# Controller_AC.net
KiCad netlist of a schematic drawn in Altium Designer
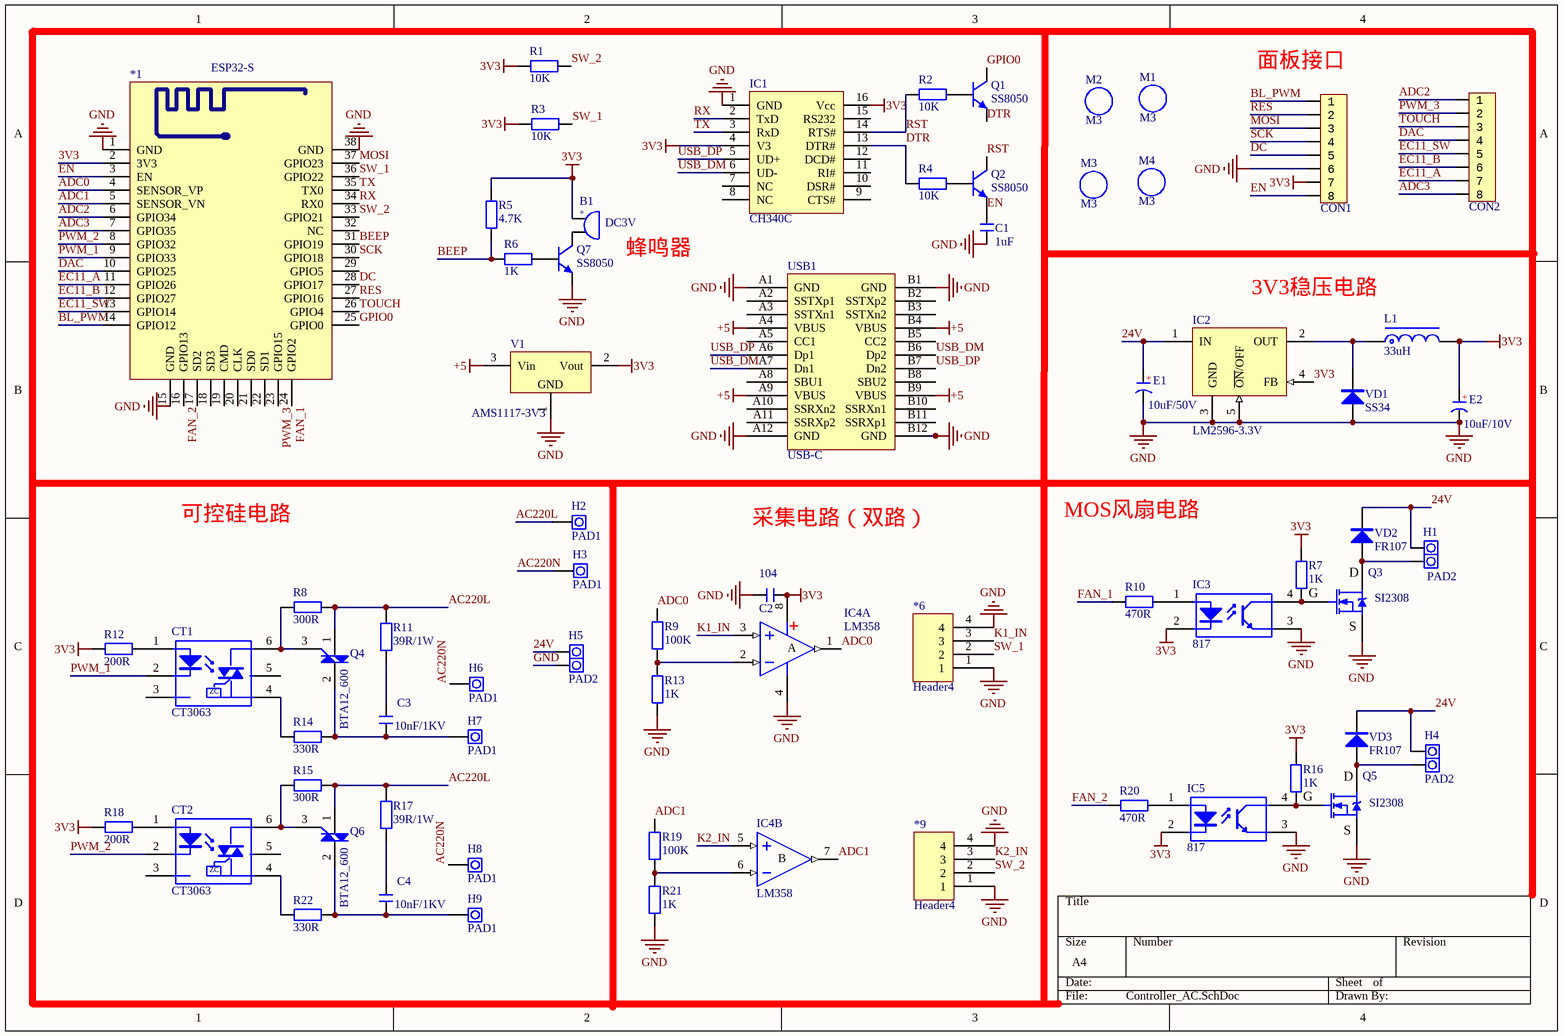
[diagram p0: Controller_AC.SchDoc]

(export (version "E")
  (design (tool "Eeschema 10.0.6"))
  (components
    (comp (ref "*1")
      (value "ESP32-S")
      (footprint "WIFIM-SMD_ESP32-C3S-2M")
      (libsource (lib "ExtendBoard") (part "ESP32-S"))
    )
    (comp (ref "*6")
      (value "Header4")
      (footprint "HDR2.54-LI-4P")
      (libsource (lib "ExtendBoard") (part "Header4"))
    )
    (comp (ref "*9")
      (value "Header4")
      (footprint "HDR2.54-LI-4P")
      (libsource (lib "ExtendBoard") (part "Header4"))
    )
    (comp (ref "B1")
      (value "DC3V")
      (footprint "BEEP 5x9x5.5")
      (description "蜂鸣器")
      (fields (field (name "版权归属") "源创客"))
      (libsource (lib "HeatPlatform") (part "BEEP"))
    )
    (comp (ref "C1")
      (value "1uF")
      (footprint "C 0603")
      (description "无极性贴片电容")
      (fields (field (name "版权归属") "源创客"))
      (libsource (lib "ExtendBoard") (part "C"))
    )
    (comp (ref "C2")
      (value "104")
      (footprint "C 0603")
      (description "无极性贴片电容")
      (fields (field (name "版权归属") "源创客"))
      (libsource (lib "ExtendBoard") (part "C"))
    )
    (comp (ref "C3")
      (value "10nF/1KV")
      (footprint "C 1206_L")
      (description "无极性贴片电容")
      (fields (field (name "版权归属") "源创客"))
      (libsource (lib "ExtendBoard") (part "C"))
    )
    (comp (ref "C4")
      (value "10nF/1KV")
      (footprint "C 1206_L")
      (description "无极性贴片电容")
      (fields (field (name "版权归属") "源创客"))
      (libsource (lib "ExtendBoard") (part "C"))
    )
    (comp (ref "CON1")
      (value "FFC_0.5_8")
      (footprint "FFC_0.5_8")
      (description "FFC")
      (libsource (lib "ExtendBoard") (part "FFC_0.5_8"))
    )
    (comp (ref "CON2")
      (value "FFC_0.5_8")
      (footprint "FFC_0.5_8")
      (description "FFC")
      (libsource (lib "ExtendBoard") (part "FFC_0.5_8"))
    )
    (comp (ref "CT1")
      (value "CT3063")
      (footprint "SMD-6-CT3063")
      (description "线性光耦（过零检测）")
      (fields (field (name "版权归属") "源创客"))
      (libsource (lib "ExtendBoard") (part "CT3063"))
    )
    (comp (ref "CT2")
      (value "CT3063")
      (footprint "SMD-6-CT3063")
      (description "线性光耦（过零检测）")
      (fields (field (name "版权归属") "源创客"))
      (libsource (lib "ExtendBoard") (part "CT3063"))
    )
    (comp (ref "E1")
      (value "10uF/50V")
      (footprint "CT 6*6 - C")
      (description "贴片固态电容")
      (fields (field (name "版权归属") "源创客"))
      (libsource (lib "ExtendBoard") (part "C-CT"))
    )
    (comp (ref "E2")
      (value "10uF/10V")
      (footprint "CT 6*6 - C")
      (description "贴片固态电容")
      (fields (field (name "版权归属") "源创客"))
      (libsource (lib "ExtendBoard") (part "C-CT"))
    )
    (comp (ref "H1")
      (value "PAD2")
      (footprint "PAD2-2.0")
      (description "引线焊盘")
      (libsource (lib "ExtendBoard") (part "PAD2"))
    )
    (comp (ref "H2")
      (value "PAD1")
      (footprint "PAD1-C")
      (description "引线焊盘")
      (libsource (lib "ExtendBoard") (part "PAD1"))
    )
    (comp (ref "H3")
      (value "PAD1")
      (footprint "PAD1-B")
      (description "引线焊盘")
      (libsource (lib "ExtendBoard") (part "PAD1"))
    )
    (comp (ref "H4")
      (value "PAD2")
      (footprint "PAD2-2.0")
      (description "引线焊盘")
      (libsource (lib "ExtendBoard") (part "PAD2"))
    )
    (comp (ref "H5")
      (value "PAD2")
      (footprint "PAD2-5.08")
      (description "引线焊盘")
      (libsource (lib "ExtendBoard") (part "PAD2"))
    )
    (comp (ref "H6")
      (value "PAD1")
      (footprint "PAD1-C")
      (description "引线焊盘")
      (libsource (lib "ExtendBoard") (part "PAD1"))
    )
    (comp (ref "H7")
      (value "PAD1")
      (footprint "PAD1-C")
      (description "引线焊盘")
      (libsource (lib "ExtendBoard") (part "PAD1"))
    )
    (comp (ref "H8")
      (value "PAD1")
      (footprint "PAD1-C")
      (description "引线焊盘")
      (libsource (lib "ExtendBoard") (part "PAD1"))
    )
    (comp (ref "H9")
      (value "PAD1")
      (footprint "PAD1-C")
      (description "引线焊盘")
      (libsource (lib "ExtendBoard") (part "PAD1"))
    )
    (comp (ref "IC1")
      (value "CH340C")
      (footprint "SOP16_N")
      (description "串口转USB")
      (libsource (lib "ExtendBoard") (part "CH340C"))
    )
    (comp (ref "IC2")
      (value "LM2596-3.3V")
      (footprint "TO263-5A")
      (description "DC降压芯片")
      (fields (field (name "版权归属") "源创客"))
      (libsource (lib "ExtendBoard") (part "LM2596"))
    )
    (comp (ref "IC3")
      (value "817")
      (footprint "SOP4-W2.54_L")
      (description "线性光耦")
      (fields (field (name "版权归属") "源创客"))
      (libsource (lib "ExtendBoard") (part "817"))
    )
    (comp (ref "IC4")
      (value "LM358")
      (footprint "SOP8_N")
      (description "双路运放")
      (libsource (lib "ExtendBoard") (part "LM358"))
    )
    (comp (ref "IC5")
      (value "817")
      (footprint "SOP4-W2.54_L")
      (description "线性光耦")
      (fields (field (name "版权归属") "源创客"))
      (libsource (lib "ExtendBoard") (part "817"))
    )
    (comp (ref "L1")
      (value "33uH")
      (footprint "CDRH127")
      (description "功率屏蔽电感")
      (fields (field (name "版权归属") "源创客"))
      (libsource (lib "ExtendBoard") (part "L-CDRH"))
    )
    (comp (ref "M1")
      (value "M3")
      (footprint "M3 125X200")
      (description "铜柱孔")
      (libsource (lib "ExtendBoard") (part "M3"))
    )
    (comp (ref "M2")
      (value "M3")
      (footprint "M3 125X200")
      (description "铜柱孔")
      (libsource (lib "ExtendBoard") (part "M3"))
    )
    (comp (ref "M3")
      (value "M3")
      (footprint "M3 125X200")
      (description "铜柱孔")
      (libsource (lib "ExtendBoard") (part "M3"))
    )
    (comp (ref "M4")
      (value "M3")
      (footprint "M3 125X200")
      (description "铜柱孔")
      (libsource (lib "ExtendBoard") (part "M3"))
    )
    (comp (ref "Q1")
      (value "SS8050")
      (footprint "SOT23-3N")
      (description "高频放大-NPN型")
      (fields (field (name "版权归属") "源创客"))
      (libsource (lib "ExtendBoard") (part "8050-SMD"))
    )
    (comp (ref "Q2")
      (value "SS8050")
      (footprint "SOT23-3N")
      (description "高频放大-NPN型")
      (fields (field (name "版权归属") "源创客"))
      (libsource (lib "ExtendBoard") (part "8050-SMD"))
    )
    (comp (ref "Q3")
      (value "SI2308")
      (footprint "SOT23-3N")
      (description "N沟道场效应管")
      (fields (field (name "版权归属") "源创客"))
      (libsource (lib "ExtendBoard") (part "SI2302"))
    )
    (comp (ref "Q4")
      (value "BTA12_600")
      (footprint "TO220A")
      (description "双向可控硅")
      (fields (field (name "版权归属") "源创客"))
      (libsource (lib "ExtendBoard") (part "BTA12_600"))
    )
    (comp (ref "Q5")
      (value "SI2308")
      (footprint "SOT23-3N")
      (description "N沟道场效应管")
      (fields (field (name "版权归属") "源创客"))
      (libsource (lib "ExtendBoard") (part "SI2302"))
    )
    (comp (ref "Q6")
      (value "BTA12_600")
      (footprint "TO220A")
      (description "双向可控硅")
      (fields (field (name "版权归属") "源创客"))
      (libsource (lib "ExtendBoard") (part "BTA12_600"))
    )
    (comp (ref "Q7")
      (value "SS8050")
      (footprint "SOT23-3N")
      (description "高频放大-NPN型")
      (fields (field (name "版权归属") "源创客"))
      (libsource (lib "ExtendBoard") (part "8050-SMD"))
    )
    (comp (ref "R1")
      (value "10K")
      (footprint "R 0603")
      (description "贴片电阻")
      (fields (field (name "版权归属") "源创客"))
      (libsource (lib "ExtendBoard") (part "R"))
    )
    (comp (ref "R2")
      (value "10K")
      (footprint "R 0603")
      (description "贴片电阻")
      (fields (field (name "版权归属") "源创客"))
      (libsource (lib "ExtendBoard") (part "R"))
    )
    (comp (ref "R3")
      (value "10K")
      (footprint "R 0603")
      (description "贴片电阻")
      (fields (field (name "版权归属") "源创客"))
      (libsource (lib "ExtendBoard") (part "R"))
    )
    (comp (ref "R4")
      (value "10K")
      (footprint "R 0603")
      (description "贴片电阻")
      (fields (field (name "版权归属") "源创客"))
      (libsource (lib "ExtendBoard") (part "R"))
    )
    (comp (ref "R5")
      (value "4.7K")
      (footprint "R 0603")
      (description "贴片电阻")
      (fields (field (name "版权归属") "源创客"))
      (libsource (lib "HeatPlatform") (part "R"))
    )
    (comp (ref "R6")
      (value "1K")
      (footprint "R 0603")
      (description "贴片电阻")
      (fields (field (name "版权归属") "源创客"))
      (libsource (lib "HeatPlatform") (part "R"))
    )
    (comp (ref "R7")
      (value "1K")
      (footprint "R 0603")
      (description "贴片电阻")
      (fields (field (name "版权归属") "源创客"))
      (libsource (lib "ExtendBoard") (part "R"))
    )
    (comp (ref "R8")
      (value "300R")
      (footprint "R 0603")
      (description "贴片电阻")
      (fields (field (name "版权归属") "源创客"))
      (libsource (lib "ExtendBoard") (part "R"))
    )
    (comp (ref "R9")
      (value "100K")
      (footprint "R 0603")
      (description "贴片电阻")
      (fields (field (name "版权归属") "源创客"))
      (libsource (lib "ExtendBoard") (part "R"))
    )
    (comp (ref "R10")
      (value "470R")
      (footprint "R 0603")
      (description "贴片电阻")
      (fields (field (name "版权归属") "源创客"))
      (libsource (lib "ExtendBoard") (part "R"))
    )
    (comp (ref "R11")
      (value "39R/1W")
      (footprint "R 2512_L")
      (description "贴片电阻")
      (fields (field (name "版权归属") "源创客"))
      (libsource (lib "ExtendBoard") (part "R"))
    )
    (comp (ref "R12")
      (value "200R")
      (footprint "R 0603")
      (description "贴片电阻")
      (fields (field (name "版权归属") "源创客"))
      (libsource (lib "ExtendBoard") (part "R"))
    )
    (comp (ref "R13")
      (value "1K")
      (footprint "R 0603")
      (description "贴片电阻")
      (fields (field (name "版权归属") "源创客"))
      (libsource (lib "ExtendBoard") (part "R"))
    )
    (comp (ref "R14")
      (value "330R")
      (footprint "R 0603")
      (description "贴片电阻")
      (fields (field (name "版权归属") "源创客"))
      (libsource (lib "ExtendBoard") (part "R"))
    )
    (comp (ref "R15")
      (value "300R")
      (footprint "R 0603")
      (description "贴片电阻")
      (fields (field (name "版权归属") "源创客"))
      (libsource (lib "ExtendBoard") (part "R"))
    )
    (comp (ref "R16")
      (value "1K")
      (footprint "R 0603")
      (description "贴片电阻")
      (fields (field (name "版权归属") "源创客"))
      (libsource (lib "ExtendBoard") (part "R"))
    )
    (comp (ref "R17")
      (value "39R/1W")
      (footprint "R 2512_L")
      (description "贴片电阻")
      (fields (field (name "版权归属") "源创客"))
      (libsource (lib "ExtendBoard") (part "R"))
    )
    (comp (ref "R18")
      (value "200R")
      (footprint "R 0603")
      (description "贴片电阻")
      (fields (field (name "版权归属") "源创客"))
      (libsource (lib "ExtendBoard") (part "R"))
    )
    (comp (ref "R19")
      (value "100K")
      (footprint "R 0603")
      (description "贴片电阻")
      (fields (field (name "版权归属") "源创客"))
      (libsource (lib "ExtendBoard") (part "R"))
    )
    (comp (ref "R20")
      (value "470R")
      (footprint "R 0603")
      (description "贴片电阻")
      (fields (field (name "版权归属") "源创客"))
      (libsource (lib "ExtendBoard") (part "R"))
    )
    (comp (ref "R21")
      (value "1K")
      (footprint "R 0603")
      (description "贴片电阻")
      (fields (field (name "版权归属") "源创客"))
      (libsource (lib "ExtendBoard") (part "R"))
    )
    (comp (ref "R22")
      (value "330R")
      (footprint "R 0603")
      (description "贴片电阻")
      (fields (field (name "版权归属") "源创客"))
      (libsource (lib "ExtendBoard") (part "R"))
    )
    (comp (ref "USB1")
      (value "USB-C")
      (footprint "USB Type-C-16Pin_A")
      (description "USB-C型母接口")
      (libsource (lib "ExtendBoard") (part "USB-C/S"))
    )
    (comp (ref "V1")
      (value "AMS1117-3V3")
      (footprint "SOT223_L")
      (description "三端稳压芯片")
      (fields (field (name "版权归属") "源创客"))
      (libsource (lib "ExtendBoard") (part "AMS1117"))
    )
    (comp (ref "VD1")
      (value "SS34")
      (footprint "SMA")
      (description "肖特基二极管")
      (fields (field (name "版权归属") "源创客"))
      (libsource (lib "ExtendBoard") (part "SS34"))
    )
    (comp (ref "VD2")
      (value "FR107")
      (footprint "SMA")
      (description "肖特基二极管")
      (fields (field (name "版权归属") "源创客"))
      (libsource (lib "ExtendBoard") (part "SS34"))
    )
    (comp (ref "VD3")
      (value "FR107")
      (footprint "SMA")
      (description "肖特基二极管")
      (fields (field (name "版权归属") "源创客"))
      (libsource (lib "ExtendBoard") (part "SS34"))
    )
  )
  (nets
    (net (code "1") (name "+5") (class "Default")
      (node (ref "USB1") (pin "A4") (pinfunction "VBUS_A4") (pintype "passive"))
      (node (ref "USB1") (pin "A9") (pinfunction "VBUS_A9") (pintype "passive"))
      (node (ref "USB1") (pin "B4") (pinfunction "VBUS_B4") (pintype "passive"))
      (node (ref "USB1") (pin "B9") (pinfunction "VBUS_B9") (pintype "passive"))
      (node (ref "V1") (pin "3") (pinfunction "Vin_3") (pintype "passive"))
    )
    (net (code "2") (name "/24V") (class "Default")
      (node (ref "E1") (pin "1") (pinfunction "A_1") (pintype "passive"))
      (node (ref "H1") (pin "1") (pinfunction "1_1") (pintype "passive"))
      (node (ref "H4") (pin "1") (pinfunction "1_1") (pintype "passive"))
      (node (ref "H5") (pin "1") (pinfunction "1_1") (pintype "passive"))
      (node (ref "IC2") (pin "1") (pinfunction "IN_1") (pintype "power_in"))
      (node (ref "VD2") (pin "2") (pinfunction "K_2") (pintype "passive"))
      (node (ref "VD3") (pin "2") (pinfunction "K_2") (pintype "passive"))
    )
    (net (code "3") (name "/AC220L") (class "Default")
      (node (ref "H2") (pin "1") (pinfunction "1_1") (pintype "passive"))
      (node (ref "Q4") (pin "1") (pinfunction "A1_1") (pintype "passive"))
      (node (ref "Q6") (pin "1") (pinfunction "A1_1") (pintype "passive"))
      (node (ref "R11") (pin "2") (pinfunction "2_2") (pintype "passive"))
      (node (ref "R15") (pin "2") (pinfunction "2_2") (pintype "passive"))
      (node (ref "R17") (pin "2") (pinfunction "2_2") (pintype "passive"))
      (node (ref "R8") (pin "2") (pinfunction "2_2") (pintype "passive"))
    )
    (net (code "4") (name "/AC220N") (class "Default")
      (node (ref "H3") (pin "1") (pinfunction "1_1") (pintype "passive"))
      (node (ref "H6") (pin "1") (pinfunction "1_1") (pintype "passive"))
      (node (ref "H8") (pin "1") (pinfunction "1_1") (pintype "passive"))
    )
    (net (code "5") (name "/ADC0") (class "Default")
      (node (ref "*1") (pin "4") (pinfunction "SENSOR_VP_4") (pintype "passive"))
      (node (ref "IC4") (pin "1") (pinfunction "OUT_1") (pintype "output"))
      (node (ref "R9") (pin "2") (pinfunction "2_2") (pintype "passive"))
    )
    (net (code "6") (name "/ADC1") (class "Default")
      (node (ref "*1") (pin "5") (pinfunction "SENSOR_VN_5") (pintype "passive"))
      (node (ref "IC4") (pin "7") (pinfunction "OUT_7") (pintype "output"))
      (node (ref "R19") (pin "2") (pinfunction "2_2") (pintype "passive"))
    )
    (net (code "7") (name "/ADC2") (class "Default")
      (node (ref "*1") (pin "6") (pinfunction "GPIO34_6") (pintype "passive"))
      (node (ref "CON2") (pin "1") (pinfunction "1_1") (pintype "passive"))
    )
    (net (code "8") (name "/ADC3") (class "Default")
      (node (ref "*1") (pin "7") (pinfunction "GPIO35_7") (pintype "passive"))
      (node (ref "CON2") (pin "8") (pinfunction "8_8") (pintype "passive"))
    )
    (net (code "9") (name "/BEEP") (class "Default")
      (node (ref "*1") (pin "31") (pinfunction "GPIO19_31") (pintype "passive"))
      (node (ref "R5") (pin "1") (pinfunction "1_1") (pintype "passive"))
      (node (ref "R6") (pin "1") (pinfunction "1_1") (pintype "passive"))
    )
    (net (code "10") (name "/BL_PWM") (class "Default")
      (node (ref "*1") (pin "14") (pinfunction "GPIO12_14") (pintype "passive"))
      (node (ref "CON1") (pin "1") (pinfunction "1_1") (pintype "passive"))
    )
    (net (code "11") (name "/DAC") (class "Default")
      (node (ref "*1") (pin "10") (pinfunction "GPIO25_10") (pintype "passive"))
      (node (ref "CON2") (pin "4") (pinfunction "4_4") (pintype "passive"))
    )
    (net (code "12") (name "/DC") (class "Default")
      (node (ref "*1") (pin "28") (pinfunction "GPIO17_28") (pintype "passive"))
      (node (ref "CON1") (pin "5") (pinfunction "5_5") (pintype "passive"))
    )
    (net (code "13") (name "/DTR") (class "Default")
      (node (ref "IC1") (pin "13") (pinfunction "DTR#_13") (pintype "passive"))
      (node (ref "Q1") (pin "2") (pinfunction "E_2") (pintype "passive"))
      (node (ref "R4") (pin "1") (pinfunction "1_1") (pintype "passive"))
    )
    (net (code "14") (name "/EC11_A") (class "Default")
      (node (ref "*1") (pin "11") (pinfunction "GPIO26_11") (pintype "passive"))
      (node (ref "CON2") (pin "7") (pinfunction "7_7") (pintype "passive"))
    )
    (net (code "15") (name "/EC11_B") (class "Default")
      (node (ref "*1") (pin "12") (pinfunction "GPIO27_12") (pintype "passive"))
      (node (ref "CON2") (pin "6") (pinfunction "6_6") (pintype "passive"))
    )
    (net (code "16") (name "/EC11_SW") (class "Default")
      (node (ref "*1") (pin "13") (pinfunction "GPIO14_13") (pintype "passive"))
      (node (ref "CON2") (pin "5") (pinfunction "5_5") (pintype "passive"))
    )
    (net (code "17") (name "/EN") (class "Default")
      (node (ref "*1") (pin "3") (pinfunction "EN_3") (pintype "passive"))
      (node (ref "C1") (pin "2") (pinfunction "2_2") (pintype "passive"))
      (node (ref "CON1") (pin "8") (pinfunction "8_8") (pintype "passive"))
      (node (ref "Q2") (pin "2") (pinfunction "E_2") (pintype "passive"))
    )
    (net (code "18") (name "/FAN_1") (class "Default")
      (node (ref "*1") (pin "24") (pinfunction "GPIO2_24") (pintype "passive"))
      (node (ref "R10") (pin "2") (pinfunction "2_2") (pintype "passive"))
    )
    (net (code "19") (name "/FAN_2") (class "Default")
      (node (ref "*1") (pin "16") (pinfunction "GPIO13_16") (pintype "passive"))
      (node (ref "R20") (pin "2") (pinfunction "2_2") (pintype "passive"))
    )
    (net (code "20") (name "/GPIO0") (class "Default")
      (node (ref "*1") (pin "25") (pinfunction "GPIO0_25") (pintype "passive"))
      (node (ref "Q1") (pin "3") (pinfunction "C_3") (pintype "passive"))
    )
    (net (code "21") (name "/K1_IN") (class "Default")
      (node (ref "*6") (pin "3") (pinfunction "3_3") (pintype "passive"))
      (node (ref "IC4") (pin "3") (pinfunction "IN+_3") (pintype "input"))
    )
    (net (code "22") (name "/K2_IN") (class "Default")
      (node (ref "*9") (pin "3") (pinfunction "3_3") (pintype "passive"))
      (node (ref "IC4") (pin "5") (pinfunction "IN+_5") (pintype "input"))
    )
    (net (code "23") (name "/MOSI") (class "Default")
      (node (ref "*1") (pin "37") (pinfunction "GPIO23_37") (pintype "passive"))
      (node (ref "CON1") (pin "3") (pinfunction "3_3") (pintype "passive"))
    )
    (net (code "24") (name "/PWM_1") (class "Default")
      (node (ref "*1") (pin "9") (pinfunction "GPIO33_9") (pintype "passive"))
      (node (ref "CT1") (pin "2") (pinfunction "C_2") (pintype "passive"))
    )
    (net (code "25") (name "/PWM_2") (class "Default")
      (node (ref "*1") (pin "8") (pinfunction "GPIO32_8") (pintype "passive"))
      (node (ref "CT2") (pin "2") (pinfunction "C_2") (pintype "passive"))
    )
    (net (code "26") (name "/PWM_3") (class "Default")
      (node (ref "*1") (pin "23") (pinfunction "GPIO15_23") (pintype "passive"))
      (node (ref "CON2") (pin "2") (pinfunction "2_2") (pintype "passive"))
    )
    (net (code "27") (name "/RES") (class "Default")
      (node (ref "*1") (pin "27") (pinfunction "GPIO16_27") (pintype "passive"))
      (node (ref "CON1") (pin "2") (pinfunction "2_2") (pintype "passive"))
    )
    (net (code "28") (name "/RST") (class "Default")
      (node (ref "IC1") (pin "14") (pinfunction "RTS#_14") (pintype "passive"))
      (node (ref "Q2") (pin "3") (pinfunction "C_3") (pintype "passive"))
      (node (ref "R2") (pin "1") (pinfunction "1_1") (pintype "passive"))
    )
    (net (code "29") (name "/RX") (class "Default")
      (node (ref "*1") (pin "34") (pinfunction "RX0_34") (pintype "passive"))
      (node (ref "IC1") (pin "2") (pinfunction "TxD_2") (pintype "passive"))
    )
    (net (code "30") (name "/SCK") (class "Default")
      (node (ref "*1") (pin "30") (pinfunction "GPIO18_30") (pintype "passive"))
      (node (ref "CON1") (pin "4") (pinfunction "4_4") (pintype "passive"))
    )
    (net (code "31") (name "/SW_1") (class "Default")
      (node (ref "*1") (pin "36") (pinfunction "GPIO22_36") (pintype "passive"))
      (node (ref "*6") (pin "2") (pinfunction "2_2") (pintype "passive"))
      (node (ref "R3") (pin "1") (pinfunction "1_1") (pintype "passive"))
    )
    (net (code "32") (name "/SW_2") (class "Default")
      (node (ref "*1") (pin "33") (pinfunction "GPIO21_33") (pintype "passive"))
      (node (ref "*9") (pin "2") (pinfunction "2_2") (pintype "passive"))
      (node (ref "R1") (pin "2") (pinfunction "2_2") (pintype "passive"))
    )
    (net (code "33") (name "/TOUCH") (class "Default")
      (node (ref "*1") (pin "26") (pinfunction "GPIO4_26") (pintype "passive"))
      (node (ref "CON2") (pin "3") (pinfunction "3_3") (pintype "passive"))
    )
    (net (code "34") (name "/TX") (class "Default")
      (node (ref "*1") (pin "35") (pinfunction "TX0_35") (pintype "passive"))
      (node (ref "IC1") (pin "3") (pinfunction "RxD_3") (pintype "passive"))
    )
    (net (code "35") (name "/USB_DM") (class "Default")
      (node (ref "IC1") (pin "6") (pinfunction "UD-_6") (pintype "passive"))
      (node (ref "USB1") (pin "A7") (pinfunction "Dn1_A7") (pintype "passive"))
      (node (ref "USB1") (pin "B6") (pinfunction "Dp2_B6") (pintype "passive"))
    )
    (net (code "36") (name "/USB_DP") (class "Default")
      (node (ref "IC1") (pin "5") (pinfunction "UD+_5") (pintype "passive"))
      (node (ref "USB1") (pin "A6") (pinfunction "Dp1_A6") (pintype "passive"))
      (node (ref "USB1") (pin "B7") (pinfunction "Dn2_B7") (pintype "passive"))
    )
    (net (code "37") (name "3V3") (class "Default")
      (node (ref "*1") (pin "2") (pinfunction "3V3_2") (pintype "passive"))
      (node (ref "B1") (pin "1") (pinfunction "1_1") (pintype "passive"))
      (node (ref "C2") (pin "2") (pinfunction "2_2") (pintype "passive"))
      (node (ref "CON1") (pin "7") (pinfunction "7_7") (pintype "passive"))
      (node (ref "E2") (pin "1") (pinfunction "A_1") (pintype "passive"))
      (node (ref "IC1") (pin "16") (pinfunction "Vcc_16") (pintype "passive"))
      (node (ref "IC1") (pin "4") (pinfunction "V3_4") (pintype "passive"))
      (node (ref "IC2") (pin "4") (pinfunction "FB_4") (pintype "input"))
      (node (ref "IC3") (pin "2") (pinfunction "K_2") (pintype "passive"))
      (node (ref "IC4") (pin "8") (pinfunction "V+_8") (pintype "power_in"))
      (node (ref "IC5") (pin "2") (pinfunction "K_2") (pintype "passive"))
      (node (ref "L1") (pin "2") (pinfunction "2_2") (pintype "passive"))
      (node (ref "R1") (pin "1") (pinfunction "1_1") (pintype "passive"))
      (node (ref "R12") (pin "1") (pinfunction "1_1") (pintype "passive"))
      (node (ref "R16") (pin "2") (pinfunction "2_2") (pintype "passive"))
      (node (ref "R18") (pin "1") (pinfunction "1_1") (pintype "passive"))
      (node (ref "R3") (pin "2") (pinfunction "2_2") (pintype "passive"))
      (node (ref "R5") (pin "2") (pinfunction "2_2") (pintype "passive"))
      (node (ref "R7") (pin "2") (pinfunction "2_2") (pintype "passive"))
      (node (ref "V1") (pin "2") (pinfunction "Vout_2") (pintype "passive"))
    )
    (net (code "38") (name "GND") (class "Default")
      (node (ref "*1") (pin "1") (pinfunction "GND_1") (pintype "passive"))
      (node (ref "*1") (pin "15") (pinfunction "GND_15") (pintype "passive"))
      (node (ref "*1") (pin "38") (pinfunction "GND_38") (pintype "passive"))
      (node (ref "*6") (pin "1") (pinfunction "1_1") (pintype "passive"))
      (node (ref "*6") (pin "4") (pinfunction "4_4") (pintype "passive"))
      (node (ref "*9") (pin "1") (pinfunction "1_1") (pintype "passive"))
      (node (ref "*9") (pin "4") (pinfunction "4_4") (pintype "passive"))
      (node (ref "C1") (pin "1") (pinfunction "1_1") (pintype "passive"))
      (node (ref "C2") (pin "1") (pinfunction "1_1") (pintype "passive"))
      (node (ref "CON1") (pin "6") (pinfunction "6_6") (pintype "passive"))
      (node (ref "E1") (pin "2") (pinfunction "K_2") (pintype "passive"))
      (node (ref "E2") (pin "2") (pinfunction "K_2") (pintype "passive"))
      (node (ref "H5") (pin "2") (pinfunction "2_2") (pintype "passive"))
      (node (ref "IC1") (pin "1") (pinfunction "GND_1") (pintype "passive"))
      (node (ref "IC2") (pin "3") (pinfunction "GND_3") (pintype "power_in"))
      (node (ref "IC2") (pin "5") (pinfunction "~{ON}/OFF_5") (pintype "input"))
      (node (ref "IC3") (pin "3") (pinfunction "E_3") (pintype "passive"))
      (node (ref "IC4") (pin "4") (pinfunction "V-_4") (pintype "power_in"))
      (node (ref "IC5") (pin "3") (pinfunction "E_3") (pintype "passive"))
      (node (ref "Q3") (pin "2") (pinfunction "S_2") (pintype "passive"))
      (node (ref "Q5") (pin "2") (pinfunction "S_2") (pintype "passive"))
      (node (ref "Q7") (pin "2") (pinfunction "E_2") (pintype "passive"))
      (node (ref "R13") (pin "1") (pinfunction "1_1") (pintype "passive"))
      (node (ref "R21") (pin "1") (pinfunction "1_1") (pintype "passive"))
      (node (ref "USB1") (pin "A1") (pinfunction "GND_A1") (pintype "passive"))
      (node (ref "USB1") (pin "A12") (pinfunction "GND_A12") (pintype "passive"))
      (node (ref "USB1") (pin "B1") (pinfunction "GND_B1") (pintype "passive"))
      (node (ref "USB1") (pin "B12") (pinfunction "GND_B12") (pintype "passive"))
      (node (ref "V1") (pin "1") (pinfunction "GND_1") (pintype "passive"))
      (node (ref "VD1") (pin "1") (pinfunction "A_1") (pintype "passive"))
    )
    (net (code "39") (name "Net-(C3-Pad2)") (class "Default")
      (node (ref "C3") (pin "2") (pinfunction "2_2") (pintype "passive"))
      (node (ref "R11") (pin "1") (pinfunction "1_1") (pintype "passive"))
    )
    (net (code "40") (name "Net-(C4-Pad2)") (class "Default")
      (node (ref "C4") (pin "2") (pinfunction "2_2") (pintype "passive"))
      (node (ref "R17") (pin "1") (pinfunction "1_1") (pintype "passive"))
    )
    (net (code "41") (name "Net-(CT1-A)") (class "Default")
      (node (ref "CT1") (pin "1") (pinfunction "A_1") (pintype "passive"))
      (node (ref "R12") (pin "2") (pinfunction "2_2") (pintype "passive"))
    )
    (net (code "42") (name "Net-(CT1-MT1)") (class "Default")
      (node (ref "CT1") (pin "6") (pinfunction "MT1_6") (pintype "passive"))
      (node (ref "Q4") (pin "3") (pinfunction "G_3") (pintype "passive"))
      (node (ref "R8") (pin "1") (pinfunction "1_1") (pintype "passive"))
    )
    (net (code "43") (name "Net-(CT1-MT2)") (class "Default")
      (node (ref "CT1") (pin "4") (pinfunction "MT2_4") (pintype "passive"))
      (node (ref "R14") (pin "1") (pinfunction "1_1") (pintype "passive"))
    )
    (net (code "44") (name "Net-(CT2-A)") (class "Default")
      (node (ref "CT2") (pin "1") (pinfunction "A_1") (pintype "passive"))
      (node (ref "R18") (pin "2") (pinfunction "2_2") (pintype "passive"))
    )
    (net (code "45") (name "Net-(CT2-MT1)") (class "Default")
      (node (ref "CT2") (pin "6") (pinfunction "MT1_6") (pintype "passive"))
      (node (ref "Q6") (pin "3") (pinfunction "G_3") (pintype "passive"))
      (node (ref "R15") (pin "1") (pinfunction "1_1") (pintype "passive"))
    )
    (net (code "46") (name "Net-(CT2-MT2)") (class "Default")
      (node (ref "CT2") (pin "4") (pinfunction "MT2_4") (pintype "passive"))
      (node (ref "R22") (pin "1") (pinfunction "1_1") (pintype "passive"))
    )
    (net (code "47") (name "Net-(IC2-OUT)") (class "Default")
      (node (ref "IC2") (pin "2") (pinfunction "OUT_2") (pintype "power_in"))
      (node (ref "L1") (pin "1") (pinfunction "1_1") (pintype "passive"))
      (node (ref "VD1") (pin "2") (pinfunction "K_2") (pintype "passive"))
    )
    (net (code "48") (name "Net-(IC3-A)") (class "Default")
      (node (ref "IC3") (pin "1") (pinfunction "A_1") (pintype "passive"))
      (node (ref "R10") (pin "1") (pinfunction "1_1") (pintype "passive"))
    )
    (net (code "49") (name "Net-(IC3-C)") (class "Default")
      (node (ref "IC3") (pin "4") (pinfunction "C_4") (pintype "passive"))
      (node (ref "Q3") (pin "1") (pinfunction "G_1") (pintype "passive"))
      (node (ref "R7") (pin "1") (pinfunction "1_1") (pintype "passive"))
    )
    (net (code "50") (name "Net-(IC4A-IN-)") (class "Default")
      (node (ref "IC4") (pin "2") (pinfunction "IN-_2") (pintype "input"))
      (node (ref "R13") (pin "2") (pinfunction "2_2") (pintype "passive"))
      (node (ref "R9") (pin "1") (pinfunction "1_1") (pintype "passive"))
    )
    (net (code "51") (name "Net-(IC4B-IN-)") (class "Default")
      (node (ref "IC4") (pin "6") (pinfunction "IN-_6") (pintype "input"))
      (node (ref "R19") (pin "1") (pinfunction "1_1") (pintype "passive"))
      (node (ref "R21") (pin "2") (pinfunction "2_2") (pintype "passive"))
    )
    (net (code "52") (name "Net-(IC5-A)") (class "Default")
      (node (ref "IC5") (pin "1") (pinfunction "A_1") (pintype "passive"))
      (node (ref "R20") (pin "1") (pinfunction "1_1") (pintype "passive"))
    )
    (net (code "53") (name "Net-(IC5-C)") (class "Default")
      (node (ref "IC5") (pin "4") (pinfunction "C_4") (pintype "passive"))
      (node (ref "Q5") (pin "1") (pinfunction "G_1") (pintype "passive"))
      (node (ref "R16") (pin "1") (pinfunction "1_1") (pintype "passive"))
    )
    (net (code "54") (name "Net-(Q1-B)") (class "Default")
      (node (ref "Q1") (pin "1") (pinfunction "B_1") (pintype "passive"))
      (node (ref "R2") (pin "2") (pinfunction "2_2") (pintype "passive"))
    )
    (net (code "55") (name "Net-(Q2-B)") (class "Default")
      (node (ref "Q2") (pin "1") (pinfunction "B_1") (pintype "passive"))
      (node (ref "R4") (pin "2") (pinfunction "2_2") (pintype "passive"))
    )
    (net (code "56") (name "Net-(Q3-D)") (class "Default")
      (node (ref "H1") (pin "2") (pinfunction "2_2") (pintype "passive"))
      (node (ref "Q3") (pin "3") (pinfunction "D_3") (pintype "passive"))
      (node (ref "VD2") (pin "1") (pinfunction "A_1") (pintype "passive"))
    )
    (net (code "57") (name "Net-(Q4-A2)") (class "Default")
      (node (ref "C3") (pin "1") (pinfunction "1_1") (pintype "passive"))
      (node (ref "H7") (pin "1") (pinfunction "1_1") (pintype "passive"))
      (node (ref "Q4") (pin "2") (pinfunction "A2_2") (pintype "passive"))
      (node (ref "R14") (pin "2") (pinfunction "2_2") (pintype "passive"))
    )
    (net (code "58") (name "Net-(Q5-D)") (class "Default")
      (node (ref "H4") (pin "2") (pinfunction "2_2") (pintype "passive"))
      (node (ref "Q5") (pin "3") (pinfunction "D_3") (pintype "passive"))
      (node (ref "VD3") (pin "1") (pinfunction "A_1") (pintype "passive"))
    )
    (net (code "59") (name "Net-(Q6-A2)") (class "Default")
      (node (ref "C4") (pin "1") (pinfunction "1_1") (pintype "passive"))
      (node (ref "H9") (pin "1") (pinfunction "1_1") (pintype "passive"))
      (node (ref "Q6") (pin "2") (pinfunction "A2_2") (pintype "passive"))
      (node (ref "R22") (pin "2") (pinfunction "2_2") (pintype "passive"))
    )
    (net (code "60") (name "Net-(Q7-B)") (class "Default")
      (node (ref "Q7") (pin "1") (pinfunction "B_1") (pintype "passive"))
      (node (ref "R6") (pin "2") (pinfunction "2_2") (pintype "passive"))
    )
    (net (code "61") (name "Net-(Q7-C)") (class "Default")
      (node (ref "B1") (pin "2") (pinfunction "2_2") (pintype "passive"))
      (node (ref "Q7") (pin "3") (pinfunction "C_3") (pintype "passive"))
    )
    (net (code "62") (name "unconnected-(*1-CLK-Pad20)") (class "Default")
      (node (ref "*1") (pin "20") (pinfunction "CLK_20") (pintype "passive"))
    )
    (net (code "63") (name "unconnected-(*1-CMD-Pad19)") (class "Default")
      (node (ref "*1") (pin "19") (pinfunction "CMD_19") (pintype "passive"))
    )
    (net (code "64") (name "unconnected-(*1-GPIO5-Pad29)") (class "Default")
      (node (ref "*1") (pin "29") (pinfunction "GPIO5_29") (pintype "passive"))
    )
    (net (code "65") (name "unconnected-(*1-NC-Pad32)") (class "Default")
      (node (ref "*1") (pin "32") (pinfunction "NC_32") (pintype "passive"))
    )
    (net (code "66") (name "unconnected-(*1-SD0-Pad21)") (class "Default")
      (node (ref "*1") (pin "21") (pinfunction "SD0_21") (pintype "passive"))
    )
    (net (code "67") (name "unconnected-(*1-SD1-Pad22)") (class "Default")
      (node (ref "*1") (pin "22") (pinfunction "SD1_22") (pintype "passive"))
    )
    (net (code "68") (name "unconnected-(*1-SD2-Pad17)") (class "Default")
      (node (ref "*1") (pin "17") (pinfunction "SD2_17") (pintype "passive"))
    )
    (net (code "69") (name "unconnected-(*1-SD3-Pad18)") (class "Default")
      (node (ref "*1") (pin "18") (pinfunction "SD3_18") (pintype "passive"))
    )
    (net (code "70") (name "unconnected-(CT1-NC-Pad3)") (class "Default")
      (node (ref "CT1") (pin "3") (pinfunction "NC_3") (pintype "passive"))
    )
    (net (code "71") (name "unconnected-(CT1-NC-Pad5)") (class "Default")
      (node (ref "CT1") (pin "5") (pinfunction "NC_5") (pintype "passive"))
    )
    (net (code "72") (name "unconnected-(CT2-NC-Pad3)") (class "Default")
      (node (ref "CT2") (pin "3") (pinfunction "NC_3") (pintype "passive"))
    )
    (net (code "73") (name "unconnected-(CT2-NC-Pad5)") (class "Default")
      (node (ref "CT2") (pin "5") (pinfunction "NC_5") (pintype "passive"))
    )
    (net (code "74") (name "unconnected-(IC1-CTS#-Pad9)") (class "Default")
      (node (ref "IC1") (pin "9") (pinfunction "CTS#_9") (pintype "passive"))
    )
    (net (code "75") (name "unconnected-(IC1-DCD#-Pad12)") (class "Default")
      (node (ref "IC1") (pin "12") (pinfunction "DCD#_12") (pintype "passive"))
    )
    (net (code "76") (name "unconnected-(IC1-DSR#-Pad10)") (class "Default")
      (node (ref "IC1") (pin "10") (pinfunction "DSR#_10") (pintype "passive"))
    )
    (net (code "77") (name "unconnected-(IC1-NC-Pad7)") (class "Default")
      (node (ref "IC1") (pin "7") (pinfunction "NC_7") (pintype "passive"))
    )
    (net (code "78") (name "unconnected-(IC1-NC-Pad8)") (class "Default")
      (node (ref "IC1") (pin "8") (pinfunction "NC_8") (pintype "passive"))
    )
    (net (code "79") (name "unconnected-(IC1-RI#-Pad11)") (class "Default")
      (node (ref "IC1") (pin "11") (pinfunction "RI#_11") (pintype "passive"))
    )
    (net (code "80") (name "unconnected-(IC1-RS232-Pad15)") (class "Default")
      (node (ref "IC1") (pin "15") (pinfunction "RS232_15") (pintype "passive"))
    )
    (net (code "81") (name "unconnected-(USB1-CC1-PadA5)") (class "Default")
      (node (ref "USB1") (pin "A5") (pinfunction "CC1_A5") (pintype "passive"))
    )
    (net (code "82") (name "unconnected-(USB1-CC2-PadB5)") (class "Default")
      (node (ref "USB1") (pin "B5") (pinfunction "CC2_B5") (pintype "passive"))
    )
    (net (code "83") (name "unconnected-(USB1-SBU1-PadA8)") (class "Default")
      (node (ref "USB1") (pin "A8") (pinfunction "SBU1_A8") (pintype "passive"))
    )
    (net (code "84") (name "unconnected-(USB1-SBU2-PadB8)") (class "Default")
      (node (ref "USB1") (pin "B8") (pinfunction "SBU2_B8") (pintype "passive"))
    )
    (net (code "85") (name "unconnected-(USB1-SSRXn1-PadB10)") (class "Default")
      (node (ref "USB1") (pin "B10") (pinfunction "SSRXn1_B10") (pintype "passive"))
    )
    (net (code "86") (name "unconnected-(USB1-SSRXn2-PadA10)") (class "Default")
      (node (ref "USB1") (pin "A10") (pinfunction "SSRXn2_A10") (pintype "passive"))
    )
    (net (code "87") (name "unconnected-(USB1-SSRXp1-PadB11)") (class "Default")
      (node (ref "USB1") (pin "B11") (pinfunction "SSRXp1_B11") (pintype "passive"))
    )
    (net (code "88") (name "unconnected-(USB1-SSRXp2-PadA11)") (class "Default")
      (node (ref "USB1") (pin "A11") (pinfunction "SSRXp2_A11") (pintype "passive"))
    )
    (net (code "89") (name "unconnected-(USB1-SSTXn1-PadA3)") (class "Default")
      (node (ref "USB1") (pin "A3") (pinfunction "SSTXn1_A3") (pintype "passive"))
    )
    (net (code "90") (name "unconnected-(USB1-SSTXn2-PadB3)") (class "Default")
      (node (ref "USB1") (pin "B3") (pinfunction "SSTXn2_B3") (pintype "passive"))
    )
    (net (code "91") (name "unconnected-(USB1-SSTXp1-PadA2)") (class "Default")
      (node (ref "USB1") (pin "A2") (pinfunction "SSTXp1_A2") (pintype "passive"))
    )
    (net (code "92") (name "unconnected-(USB1-SSTXp2-PadB2)") (class "Default")
      (node (ref "USB1") (pin "B2") (pinfunction "SSTXp2_B2") (pintype "passive"))
    )
  )
)
